# STM32_microcontroller_IOs.net
KiCad netlist of a schematic drawn in Altium Designer
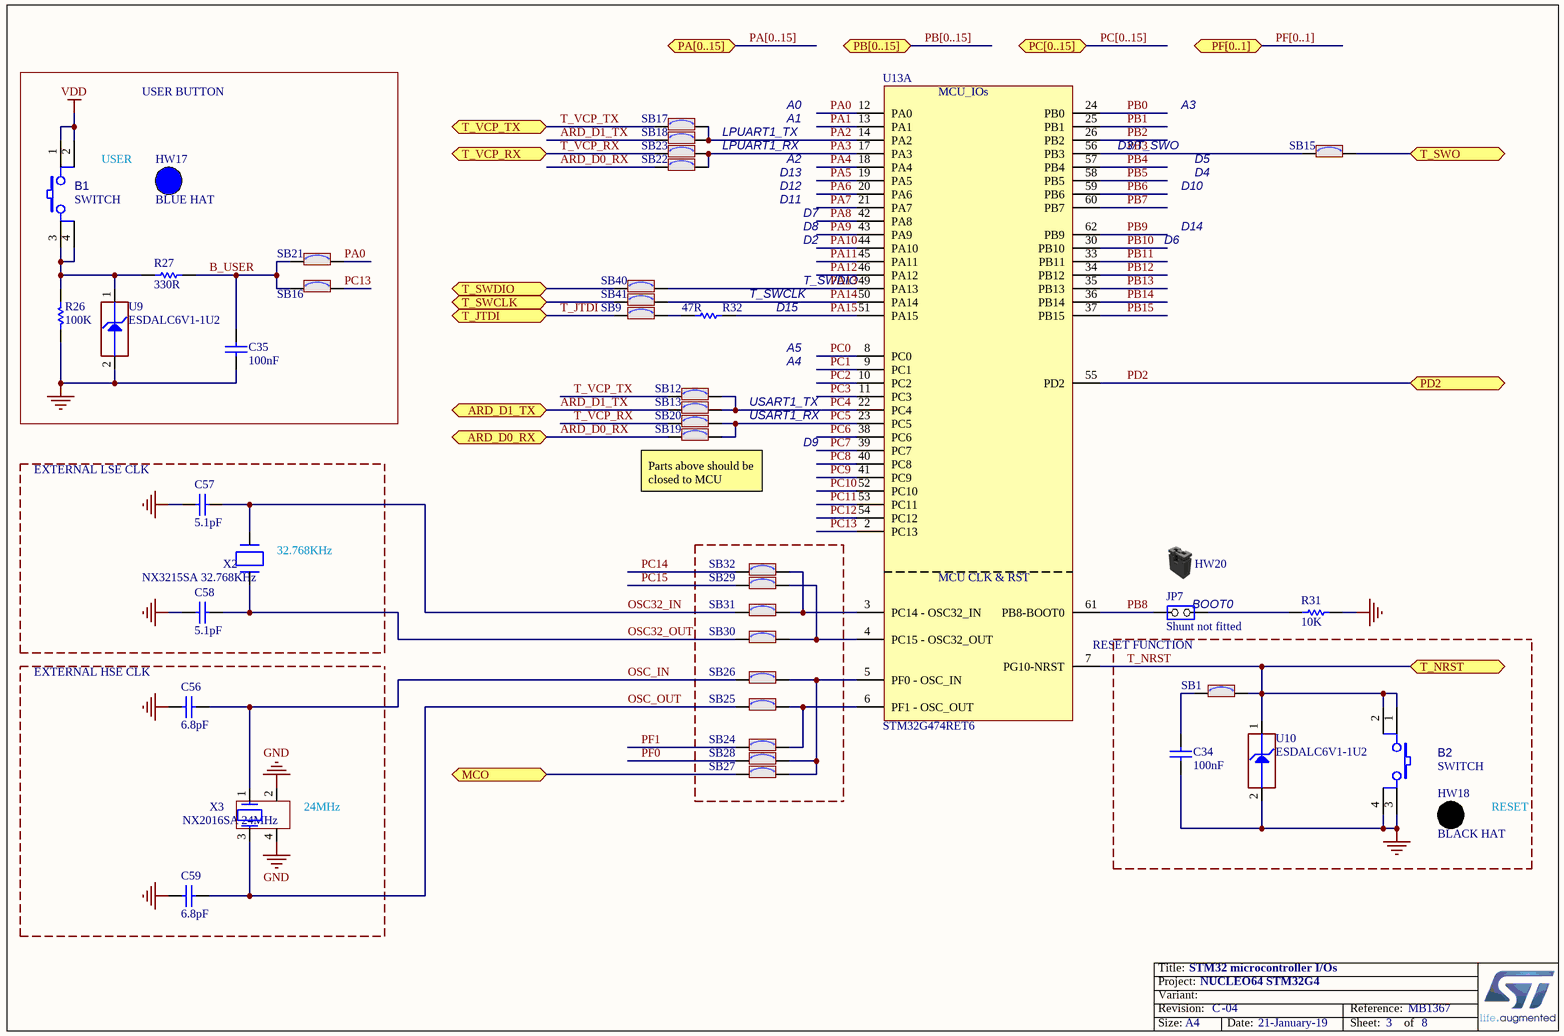
[diagram p0: STM32_microcontroller_IOs.SchDoc]

(export (version "E")
  (design (tool "Eeschema 10.0.6"))
  (components
    (comp (ref "B1")
      (value "SWITCH")
      (footprint "SWI_WEALTHMETAL_TD-0341_4P_BLUE")
      (description "Non-Open Push-Button 0.1A 24V")
      (fields
        (field (name "INTERNAL_PART_NUMBER") "MCD-00002")
        (field (name "MANUFACTURER_PART_NUMBER") "TD-0341")
        (field (name "PROVIDED_BY") "SUBCO")
      )
      (libsource (lib "MCD_PARTS_database") (part "SW-PUSH-CMS"))
    )
    (comp (ref "B2")
      (value "SWITCH")
      (footprint "SWI_WEALTHMETAL_TD-0341_4P_BLACK")
      (description "Non-Open Push-Button 0.1A 24V BLACK")
      (fields
        (field (name "INTERNAL_PART_NUMBER") "MCD-00001")
        (field (name "MANUFACTURER_PART_NUMBER") "TD-0341")
        (field (name "PROVIDED_BY") "SUBCO")
      )
      (libsource (lib "MCD_PARTS_database") (part "SW-PUSH-CMS"))
    )
    (comp (ref "C34")
      (value "100nF")
      (footprint "C0402")
      (description "Capacitor, MLCC, 100nF, 16V, X7R, 10%, 0402, T=0,5mm")
      (fields
        (field (name "INTERNAL_PART_NUMBER") "MCD-00102")
        (field (name "MANUFACTURER_PART_NUMBER") "CC0402KRX7R7BB104")
        (field (name "PROVIDED_BY") "Subcon")
      )
      (libsource (lib "MCD_PARTS_database") (part "Capacitor"))
    )
    (comp (ref "C35")
      (value "100nF")
      (footprint "C0402")
      (description "Capacitor, MLCC, 100nF, 16V, X7R, 10%, 0402, T=0,5mm")
      (fields
        (field (name "INTERNAL_PART_NUMBER") "MCD-00102")
        (field (name "MANUFACTURER_PART_NUMBER") "CC0402KRX7R7BB104")
        (field (name "PROVIDED_BY") "Subcon")
      )
      (libsource (lib "MCD_PARTS_database") (part "Capacitor"))
    )
    (comp (ref "C56")
      (value "6.8pF")
      (footprint "C0402")
      (description "Capacitor, MLCC, 6.8pF, 50V, NPO, +-0.25pF, 0402, T=0.5mm")
      (fields
        (field (name "INTERNAL_PART_NUMBER") "MCD-00674")
        (field (name "MANUFACTURER_PART_NUMBER") "CC0402CRNPO9BN6R8")
        (field (name "PROVIDED_BY") "SUBCO")
      )
      (libsource (lib "MCD_PARTS_database") (part "Capacitor"))
    )
    (comp (ref "C57")
      (value "5.1pF")
      (footprint "C0402")
      (description "Capacitor, MLCC, 5.1pF, 50V, NPO, +-0.25pF, 0402, T=0.5mm")
      (fields
        (field (name "INTERNAL_PART_NUMBER") "MCD-00003")
        (field (name "MANUFACTURER_PART_NUMBER") "CC0402CRNPO9BN5R1")
        (field (name "PROVIDED_BY") "SUBCO")
      )
      (libsource (lib "MCD_PARTS_database") (part "Capacitor"))
    )
    (comp (ref "C58")
      (value "5.1pF")
      (footprint "C0402")
      (description "Capacitor, MLCC, 5.1pF, 50V, NPO, +-0.25pF, 0402, T=0.5mm")
      (fields
        (field (name "INTERNAL_PART_NUMBER") "MCD-00003")
        (field (name "MANUFACTURER_PART_NUMBER") "CC0402CRNPO9BN5R1")
        (field (name "PROVIDED_BY") "SUBCO")
      )
      (libsource (lib "MCD_PARTS_database") (part "Capacitor"))
    )
    (comp (ref "C59")
      (value "6.8pF")
      (footprint "C0402")
      (description "Capacitor, MLCC, 6.8pF, 50V, NPO, +-0.25pF, 0402, T=0.5mm")
      (fields
        (field (name "INTERNAL_PART_NUMBER") "MCD-00674")
        (field (name "MANUFACTURER_PART_NUMBER") "CC0402CRNPO9BN6R8")
        (field (name "PROVIDED_BY") "SUBCO")
      )
      (libsource (lib "MCD_PARTS_database") (part "Capacitor"))
    )
    (comp (ref "HW17")
      (value "BLUE HAT")
      (description "Blue Hat for switch TD0341X-G01-BLU")
      (fields
        (field (name "INTERNAL_PART_NUMBER") "MCD-00634")
        (field (name "MANUFACTURER_PART_NUMBER") "988.16.09.3.00002_SH-517")
        (field (name "PROVIDED_BY") "SUBCO")
      )
      (libsource (lib "MCD_PARTS_database") (part "BUTTON_HAT_BLUE"))
    )
    (comp (ref "HW18")
      (value "BLACK HAT")
      (description "Black Hat for switch TD0341X-G01-BLA")
      (fields
        (field (name "INTERNAL_PART_NUMBER") "MCD-00635")
        (field (name "MANUFACTURER_PART_NUMBER") "988.16.09.3.00003_SH-517")
        (field (name "PROVIDED_BY") "SUBCO")
      )
      (libsource (lib "MCD_PARTS_database") (part "BUTTON_HAT_BLACK"))
    )
    (comp (ref "HW20")
      (value "~")
      (description "SHUNT 2.54mm BLACK")
      (fields
        (field (name "INTERNAL_PART_NUMBER") "MCD-00043")
        (field (name "MANUFACTURER_PART_NUMBER") "SNT-100-BK-G")
        (field (name "PROVIDED_BY") "Subcon")
      )
      (libsource (lib "MCD_PARTS_database") (part "Shunt Black 2.54mm"))
    )
    (comp (ref "JP7")
      (value "Shunt not fitted")
      (footprint "CON_SAMTEC_TSW-102-07-G-S")
      (description "Header, 2x1, 2,54mm, VR, TH, Height 5.84mm/2.54mm")
      (fields
        (field (name "INTERNAL_PART_NUMBER") "MCD-00045")
        (field (name "MANUFACTURER_PART_NUMBER") "TSW-102-07-x-S")
        (field (name "PROVIDED_BY") "Subcon")
      )
      (libsource (lib "MCD_PARTS_database") (part "Jumper_Header 2x1"))
    )
    (comp (ref "R26")
      (value "100K")
      (footprint "R0603")
      (description "Resistor,100K,0603,1%,1/10W")
      (fields
        (field (name "INTERNAL_PART_NUMBER") "MCD-00223")
        (field (name "MANUFACTURER_PART_NUMBER") "RC0603FR-07100KL")
        (field (name "PROVIDED_BY") "Subcon")
      )
      (libsource (lib "MCD_PARTS_database") (part "Resistor"))
    )
    (comp (ref "R27")
      (value "330R")
      (footprint "R0603")
      (description "Resistor,330R,0603,1%,1/10W")
      (fields
        (field (name "INTERNAL_PART_NUMBER") "MCD-00197")
        (field (name "MANUFACTURER_PART_NUMBER") "RC0603FR-07330RL")
        (field (name "PROVIDED_BY") "Subcon")
      )
      (libsource (lib "MCD_PARTS_database") (part "Resistor"))
    )
    (comp (ref "R31")
      (value "10K")
      (footprint "R0603")
      (description "Resistor,10K,0603,1%,1/10W")
      (fields
        (field (name "INTERNAL_PART_NUMBER") "MCD-00220")
        (field (name "MANUFACTURER_PART_NUMBER") "RC0603FR-0710KL")
        (field (name "PROVIDED_BY") "Subcon")
      )
      (libsource (lib "MCD_PARTS_database") (part "Resistor"))
    )
    (comp (ref "R32")
      (value "47R")
      (footprint "R0402")
      (description "Resistor,47R,0402,1%,1/16W")
      (fields
        (field (name "INTERNAL_PART_NUMBER") "MCD-00481")
        (field (name "MANUFACTURER_PART_NUMBER") "RC0402FR-0747RL")
        (field (name "PROVIDED_BY") "SUBCO")
      )
      (libsource (lib "MCD_PARTS_database") (part "Resistor"))
    )
    (comp (ref "SB1")
      (value "~")
      (footprint "SOLDER-BRIDGE_R0603-0R")
      (description "Solder Bridge ON")
      (fields
        (field (name "INTERNAL_PART_NUMBER") "MCD-00071")
        (field (name "MANUFACTURER_PART_NUMBER") "RC0603JR-070RL")
        (field (name "PROVIDED_BY") "SUBCO")
      )
      (libsource (lib "MCD_PARTS_database") (part "SB_ON"))
    )
    (comp (ref "SB9")
      (value "~")
      (footprint "SOLDER-BRIDGE_R0603-0R")
      (description "Solder Bridge ON")
      (fields
        (field (name "INTERNAL_PART_NUMBER") "MCD-00071")
        (field (name "MANUFACTURER_PART_NUMBER") "RC0603JR-070RL")
        (field (name "PROVIDED_BY") "SUBCO")
      )
      (libsource (lib "MCD_PARTS_database") (part "SB_ON"))
    )
    (comp (ref "SB12")
      (value "~")
      (footprint "SOLDER-BRIDGE_R0603-0R")
      (description "Solder Bridge ON")
      (fields
        (field (name "INTERNAL_PART_NUMBER") "MCD-00071")
        (field (name "MANUFACTURER_PART_NUMBER") "RC0603JR-070RL")
        (field (name "PROVIDED_BY") "SUBCO")
      )
      (libsource (lib "MCD_PARTS_database") (part "SB_ON"))
    )
    (comp (ref "SB13")
      (value "~")
      (footprint "SOLDER-BRIDGE_R0603-0R")
      (description "Solder Bridge ON")
      (fields
        (field (name "INTERNAL_PART_NUMBER") "MCD-00071")
        (field (name "MANUFACTURER_PART_NUMBER") "RC0603JR-070RL")
        (field (name "PROVIDED_BY") "SUBCO")
      )
      (libsource (lib "") (part "SB_ON_1"))
    )
    (comp (ref "SB15")
      (value "~")
      (footprint "SOLDER-BRIDGE_R0603-0R")
      (description "Solder Bridge ON")
      (fields
        (field (name "INTERNAL_PART_NUMBER") "MCD-00071")
        (field (name "MANUFACTURER_PART_NUMBER") "RC0603JR-070RL")
        (field (name "PROVIDED_BY") "SUBCO")
      )
      (libsource (lib "MCD_PARTS_database") (part "SB_ON"))
    )
    (comp (ref "SB16")
      (value "~")
      (footprint "SOLDER-BRIDGE_R0603-0R")
      (description "Solder Bridge ON")
      (fields
        (field (name "INTERNAL_PART_NUMBER") "MCD-00071")
        (field (name "MANUFACTURER_PART_NUMBER") "RC0603JR-070RL")
        (field (name "PROVIDED_BY") "SUBCO")
      )
      (libsource (lib "MCD_PARTS_database") (part "SB_ON"))
    )
    (comp (ref "SB17")
      (value "~")
      (footprint "SOLDER-BRIDGE_R0603-0R")
      (description "Solder Bridge ON")
      (fields
        (field (name "INTERNAL_PART_NUMBER") "MCD-00071")
        (field (name "MANUFACTURER_PART_NUMBER") "RC0603JR-070RL")
        (field (name "PROVIDED_BY") "SUBCO")
      )
      (libsource (lib "MCD_PARTS_database") (part "SB_ON"))
    )
    (comp (ref "SB18")
      (value "~")
      (footprint "SOLDER-BRIDGE_R0603-0R")
      (description "Solder Bridge ON")
      (fields
        (field (name "INTERNAL_PART_NUMBER") "MCD-00071")
        (field (name "MANUFACTURER_PART_NUMBER") "RC0603JR-070RL")
        (field (name "PROVIDED_BY") "SUBCO")
      )
      (libsource (lib "") (part "SB_ON_1"))
    )
    (comp (ref "SB19")
      (value "~")
      (footprint "SOLDER-BRIDGE_R0603-0R")
      (description "Solder Bridge ON")
      (fields
        (field (name "INTERNAL_PART_NUMBER") "MCD-00071")
        (field (name "MANUFACTURER_PART_NUMBER") "RC0603JR-070RL")
        (field (name "PROVIDED_BY") "SUBCO")
      )
      (libsource (lib "") (part "SB_ON_1"))
    )
    (comp (ref "SB20")
      (value "~")
      (footprint "SOLDER-BRIDGE_R0603-0R")
      (description "Solder Bridge ON")
      (fields
        (field (name "INTERNAL_PART_NUMBER") "MCD-00071")
        (field (name "MANUFACTURER_PART_NUMBER") "RC0603JR-070RL")
        (field (name "PROVIDED_BY") "SUBCO")
      )
      (libsource (lib "MCD_PARTS_database") (part "SB_ON"))
    )
    (comp (ref "SB21")
      (value "~")
      (footprint "SOLDER-BRIDGE_R0603-0R")
      (description "Solder Bridge ON")
      (fields
        (field (name "INTERNAL_PART_NUMBER") "MCD-00071")
        (field (name "MANUFACTURER_PART_NUMBER") "RC0603JR-070RL")
        (field (name "PROVIDED_BY") "SUBCO")
      )
      (libsource (lib "MCD_PARTS_database") (part "SB_ON"))
    )
    (comp (ref "SB22")
      (value "~")
      (footprint "SOLDER-BRIDGE_R0603-0R")
      (description "Solder Bridge ON")
      (fields
        (field (name "INTERNAL_PART_NUMBER") "MCD-00071")
        (field (name "MANUFACTURER_PART_NUMBER") "RC0603JR-070RL")
        (field (name "PROVIDED_BY") "SUBCO")
      )
      (libsource (lib "") (part "SB_ON_1"))
    )
    (comp (ref "SB23")
      (value "~")
      (footprint "SOLDER-BRIDGE_R0603-0R")
      (description "Solder Bridge ON")
      (fields
        (field (name "INTERNAL_PART_NUMBER") "MCD-00071")
        (field (name "MANUFACTURER_PART_NUMBER") "RC0603JR-070RL")
        (field (name "PROVIDED_BY") "SUBCO")
      )
      (libsource (lib "MCD_PARTS_database") (part "SB_ON"))
    )
    (comp (ref "SB24")
      (value "~")
      (footprint "SOLDER-BRIDGE_R0603-0R")
      (description "Solder Bridge ON")
      (fields
        (field (name "INTERNAL_PART_NUMBER") "MCD-00071")
        (field (name "MANUFACTURER_PART_NUMBER") "RC0603JR-070RL")
        (field (name "PROVIDED_BY") "SUBCO")
      )
      (libsource (lib "MCD_PARTS_database") (part "SB_ON"))
    )
    (comp (ref "SB25")
      (value "~")
      (footprint "SOLDER-BRIDGE_R0603-0R")
      (description "Solder Bridge ON")
      (fields
        (field (name "INTERNAL_PART_NUMBER") "MCD-00071")
        (field (name "MANUFACTURER_PART_NUMBER") "RC0603JR-070RL")
        (field (name "PROVIDED_BY") "SUBCO")
      )
      (libsource (lib "MCD_PARTS_database") (part "SB_ON"))
    )
    (comp (ref "SB26")
      (value "~")
      (footprint "SOLDER-BRIDGE_R0603-0R")
      (description "Solder Bridge ON")
      (fields
        (field (name "INTERNAL_PART_NUMBER") "MCD-00071")
        (field (name "MANUFACTURER_PART_NUMBER") "RC0603JR-070RL")
        (field (name "PROVIDED_BY") "SUBCO")
      )
      (libsource (lib "MCD_PARTS_database") (part "SB_ON"))
    )
    (comp (ref "SB27")
      (value "~")
      (footprint "SOLDER-BRIDGE_R0603-0R")
      (description "Solder Bridge ON")
      (fields
        (field (name "INTERNAL_PART_NUMBER") "MCD-00071")
        (field (name "MANUFACTURER_PART_NUMBER") "RC0603JR-070RL")
        (field (name "PROVIDED_BY") "SUBCO")
      )
      (libsource (lib "MCD_PARTS_database") (part "SB_ON"))
    )
    (comp (ref "SB28")
      (value "~")
      (footprint "SOLDER-BRIDGE_R0603-0R")
      (description "Solder Bridge ON")
      (fields
        (field (name "INTERNAL_PART_NUMBER") "MCD-00071")
        (field (name "MANUFACTURER_PART_NUMBER") "RC0603JR-070RL")
        (field (name "PROVIDED_BY") "SUBCO")
      )
      (libsource (lib "MCD_PARTS_database") (part "SB_ON"))
    )
    (comp (ref "SB29")
      (value "~")
      (footprint "SOLDER-BRIDGE_R0603-0R")
      (description "Solder Bridge ON")
      (fields
        (field (name "INTERNAL_PART_NUMBER") "MCD-00071")
        (field (name "MANUFACTURER_PART_NUMBER") "RC0603JR-070RL")
        (field (name "PROVIDED_BY") "SUBCO")
      )
      (libsource (lib "MCD_PARTS_database") (part "SB_ON"))
    )
    (comp (ref "SB30")
      (value "~")
      (footprint "SOLDER-BRIDGE_R0603-0R")
      (description "Solder Bridge ON")
      (fields
        (field (name "INTERNAL_PART_NUMBER") "MCD-00071")
        (field (name "MANUFACTURER_PART_NUMBER") "RC0603JR-070RL")
        (field (name "PROVIDED_BY") "SUBCO")
      )
      (libsource (lib "MCD_PARTS_database") (part "SB_ON"))
    )
    (comp (ref "SB31")
      (value "~")
      (footprint "SOLDER-BRIDGE_R0603-0R")
      (description "Solder Bridge ON")
      (fields
        (field (name "INTERNAL_PART_NUMBER") "MCD-00071")
        (field (name "MANUFACTURER_PART_NUMBER") "RC0603JR-070RL")
        (field (name "PROVIDED_BY") "SUBCO")
      )
      (libsource (lib "MCD_PARTS_database") (part "SB_ON"))
    )
    (comp (ref "SB32")
      (value "~")
      (footprint "SOLDER-BRIDGE_R0603-0R")
      (description "Solder Bridge ON")
      (fields
        (field (name "INTERNAL_PART_NUMBER") "MCD-00071")
        (field (name "MANUFACTURER_PART_NUMBER") "RC0603JR-070RL")
        (field (name "PROVIDED_BY") "SUBCO")
      )
      (libsource (lib "MCD_PARTS_database") (part "SB_ON"))
    )
    (comp (ref "SB40")
      (value "~")
      (footprint "SOLDER-BRIDGE_R0603-0R")
      (description "Solder Bridge ON")
      (fields
        (field (name "INTERNAL_PART_NUMBER") "MCD-00071")
        (field (name "MANUFACTURER_PART_NUMBER") "RC0603JR-070RL")
        (field (name "PROVIDED_BY") "SUBCO")
      )
      (libsource (lib "MCD_PARTS_database") (part "SB_ON"))
    )
    (comp (ref "SB41")
      (value "~")
      (footprint "SOLDER-BRIDGE_R0603-0R")
      (description "Solder Bridge ON")
      (fields
        (field (name "INTERNAL_PART_NUMBER") "MCD-00071")
        (field (name "MANUFACTURER_PART_NUMBER") "RC0603JR-070RL")
        (field (name "PROVIDED_BY") "SUBCO")
      )
      (libsource (lib "MCD_PARTS_database") (part "SB_ON"))
    )
    (comp (ref "U9")
      (value "ESDALC6V1-1U2")
      (footprint "ESD_ST0201")
      (description "ESD protection 6V1")
      (fields
        (field (name "INTERNAL_PART_NUMBER") "MCD-00170")
        (field (name "MANUFACTURER") "STMICROELECTRONICS")
        (field (name "PROVIDED_BY") "Subcon")
      )
      (libsource (lib "MCD_PARTS_database") (part "ESD-TRANSIL"))
    )
    (comp (ref "U10")
      (value "ESDALC6V1-1U2")
      (footprint "ESD_ST0201")
      (description "ESD protection 6V1")
      (fields
        (field (name "INTERNAL_PART_NUMBER") "MCD-00170")
        (field (name "MANUFACTURER") "STMICROELECTRONICS")
        (field (name "PROVIDED_BY") "Subcon")
      )
      (libsource (lib "MCD_PARTS_database") (part "ESD-TRANSIL"))
    )
    (comp (ref "U13")
      (value "STM32G474RET6")
      (footprint "ICC_LQFP64_10X10_P050_SOCKET_YAMAICHI_IC149-064-069-B5_NM")
      (description "STM32G474, LQFP64 package,  3D IC footprint with 2D socket footprint.")
      (fields
        (field (name "INTERNAL_PART_NUMBER") "MCD-01243")
        (field (name "MANUFACTURER") "STMICROELECTRONICS")
        (field (name "PROVIDED_BY") "SUBCO with ST control")
      )
      (libsource (lib "MCD_PARTS_database") (part "STM32G4xx_LQFP64"))
    )
    (comp (ref "X2")
      (value "NX3215SA 32.768KHz")
      (footprint "CRY_NX3215SA_2P")
      (description "Crystal 32.768kHz, 6pF, +-20ppm, 50Kohms max, SMD")
      (fields
        (field (name "INTERNAL_PART_NUMBER") "MCD-00091")
        (field (name "MANUFACTURER_PART_NUMBER") "NX3215SA 32.768KHz EXS00A-MU00525")
        (field (name "PROVIDED_BY") "SUBCO")
      )
      (libsource (lib "MCD_PARTS_database") (part "XTAL_2_PINS"))
    )
    (comp (ref "X3")
      (value "NX2016SA 24MHz")
      (footprint "CRY_NX2016SA_4P")
      (description "Crystal 24MHz, 6pF, +-20ppm, 80ohms max, SMD")
      (fields
        (field (name "INTERNAL_PART_NUMBER") "MCD-01036")
        (field (name "MANUFACTURER_PART_NUMBER") "NX2016SA 24MHz EXS00A-CS10820")
        (field (name "PROVIDED_BY") "SUBCO")
      )
      (libsource (lib "MCD_PARTS_database") (part "XTAL_4_PINS"))
    )
  )
  (nets
    (net (code "1") (name "/ARD_D0_RX") (class "Default")
      (node (ref "SB19") (pin "2") (pinfunction "2_2") (pintype "passive"))
      (node (ref "SB22") (pin "2") (pinfunction "2_2") (pintype "passive"))
    )
    (net (code "2") (name "/ARD_D1_TX") (class "Default")
      (node (ref "SB13") (pin "2") (pinfunction "2_2") (pintype "passive"))
      (node (ref "SB18") (pin "2") (pinfunction "2_2") (pintype "passive"))
    )
    (net (code "3") (name "/B_USER") (class "Default")
      (node (ref "C35") (pin "2") (pinfunction "2_2") (pintype "passive"))
      (node (ref "R27") (pin "2") (pinfunction "2_2") (pintype "passive"))
      (node (ref "SB16") (pin "1") (pinfunction "1_1") (pintype "passive"))
      (node (ref "SB21") (pin "1") (pinfunction "1_1") (pintype "passive"))
    )
    (net (code "4") (name "/MCO") (class "Default")
      (node (ref "SB27") (pin "1") (pinfunction "1_1") (pintype "passive"))
    )
    (net (code "5") (name "/OSC32_IN") (class "Default")
      (node (ref "C57") (pin "1") (pinfunction "1_1") (pintype "passive"))
      (node (ref "SB31") (pin "1") (pinfunction "1_1") (pintype "passive"))
      (node (ref "X2") (pin "2") (pinfunction "X2_2") (pintype "passive"))
    )
    (net (code "6") (name "/OSC32_OUT") (class "Default")
      (node (ref "C58") (pin "1") (pinfunction "1_1") (pintype "passive"))
      (node (ref "SB30") (pin "1") (pinfunction "1_1") (pintype "passive"))
      (node (ref "X2") (pin "1") (pinfunction "X1_1") (pintype "passive"))
    )
    (net (code "7") (name "/OSC_IN") (class "Default")
      (node (ref "C56") (pin "2") (pinfunction "2_2") (pintype "passive"))
      (node (ref "SB26") (pin "1") (pinfunction "1_1") (pintype "passive"))
      (node (ref "X3") (pin "1") (pinfunction "1_1") (pintype "passive"))
    )
    (net (code "8") (name "/OSC_OUT") (class "Default")
      (node (ref "C59") (pin "2") (pinfunction "2_2") (pintype "passive"))
      (node (ref "SB25") (pin "1") (pinfunction "1_1") (pintype "passive"))
      (node (ref "X3") (pin "3") (pinfunction "3_3") (pintype "passive"))
    )
    (net (code "9") (name "/PA0") (class "Default")
      (node (ref "SB21") (pin "2") (pinfunction "2_2") (pintype "passive"))
      (node (ref "U13") (pin "12") (pinfunction "PA0_12") (pintype "passive"))
    )
    (net (code "10") (name "/PA1") (class "Default")
      (node (ref "U13") (pin "13") (pinfunction "PA1_13") (pintype "passive"))
    )
    (net (code "11") (name "/PA2") (class "Default")
      (node (ref "SB17") (pin "2") (pinfunction "2_2") (pintype "passive"))
      (node (ref "SB18") (pin "1") (pinfunction "1_1") (pintype "passive"))
      (node (ref "U13") (pin "14") (pinfunction "PA2_14") (pintype "passive"))
    )
    (net (code "12") (name "/PA3") (class "Default")
      (node (ref "SB22") (pin "1") (pinfunction "1_1") (pintype "passive"))
      (node (ref "SB23") (pin "2") (pinfunction "2_2") (pintype "passive"))
      (node (ref "U13") (pin "17") (pinfunction "PA3_17") (pintype "passive"))
    )
    (net (code "13") (name "/PA4") (class "Default")
      (node (ref "U13") (pin "18") (pinfunction "PA4_18") (pintype "passive"))
    )
    (net (code "14") (name "/PA5") (class "Default")
      (node (ref "U13") (pin "19") (pinfunction "PA5_19") (pintype "passive"))
    )
    (net (code "15") (name "/PA6") (class "Default")
      (node (ref "U13") (pin "20") (pinfunction "PA6_20") (pintype "passive"))
    )
    (net (code "16") (name "/PA7") (class "Default")
      (node (ref "U13") (pin "21") (pinfunction "PA7_21") (pintype "passive"))
    )
    (net (code "17") (name "/PA8") (class "Default")
      (node (ref "U13") (pin "42") (pinfunction "PA8_42") (pintype "passive"))
    )
    (net (code "18") (name "/PA9") (class "Default")
      (node (ref "U13") (pin "43") (pinfunction "PA9_43") (pintype "passive"))
    )
    (net (code "19") (name "/PA10") (class "Default")
      (node (ref "U13") (pin "44") (pinfunction "PA10_44") (pintype "passive"))
    )
    (net (code "20") (name "/PA11") (class "Default")
      (node (ref "U13") (pin "45") (pinfunction "PA11_45") (pintype "passive"))
    )
    (net (code "21") (name "/PA12") (class "Default")
      (node (ref "U13") (pin "46") (pinfunction "PA12_46") (pintype "passive"))
    )
    (net (code "22") (name "/PA13") (class "Default")
      (node (ref "SB40") (pin "2") (pinfunction "2_2") (pintype "passive"))
      (node (ref "U13") (pin "49") (pinfunction "PA13_49") (pintype "passive"))
    )
    (net (code "23") (name "/PA14") (class "Default")
      (node (ref "SB41") (pin "2") (pinfunction "2_2") (pintype "passive"))
      (node (ref "U13") (pin "50") (pinfunction "PA14_50") (pintype "passive"))
    )
    (net (code "24") (name "/PA15") (class "Default")
      (node (ref "R32") (pin "2") (pinfunction "2_2") (pintype "passive"))
      (node (ref "U13") (pin "51") (pinfunction "PA15_51") (pintype "passive"))
    )
    (net (code "26") (name "/PB0") (class "Default")
      (node (ref "U13") (pin "24") (pinfunction "PB0_24") (pintype "passive"))
    )
    (net (code "27") (name "/PB1") (class "Default")
      (node (ref "U13") (pin "25") (pinfunction "PB1_25") (pintype "passive"))
    )
    (net (code "28") (name "/PB2") (class "Default")
      (node (ref "U13") (pin "26") (pinfunction "PB2_26") (pintype "passive"))
    )
    (net (code "29") (name "/PB3") (class "Default")
      (node (ref "SB15") (pin "1") (pinfunction "1_1") (pintype "passive"))
      (node (ref "U13") (pin "56") (pinfunction "PB3_56") (pintype "passive"))
    )
    (net (code "30") (name "/PB4") (class "Default")
      (node (ref "U13") (pin "57") (pinfunction "PB4_57") (pintype "passive"))
    )
    (net (code "31") (name "/PB5") (class "Default")
      (node (ref "U13") (pin "58") (pinfunction "PB5_58") (pintype "passive"))
    )
    (net (code "32") (name "/PB6") (class "Default")
      (node (ref "U13") (pin "59") (pinfunction "PB6_59") (pintype "passive"))
    )
    (net (code "33") (name "/PB7") (class "Default")
      (node (ref "U13") (pin "60") (pinfunction "PB7_60") (pintype "passive"))
    )
    (net (code "34") (name "/PB8") (class "Default")
      (node (ref "JP7") (pin "1") (pinfunction "COMMON_1") (pintype "passive"))
      (node (ref "U13") (pin "61") (pinfunction "PB8-BOOT0_61") (pintype "passive"))
    )
    (net (code "35") (name "/PB9") (class "Default")
      (node (ref "U13") (pin "62") (pinfunction "PB9_62") (pintype "passive"))
    )
    (net (code "36") (name "/PB10") (class "Default")
      (node (ref "U13") (pin "30") (pinfunction "PB10_30") (pintype "passive"))
    )
    (net (code "37") (name "/PB11") (class "Default")
      (node (ref "U13") (pin "33") (pinfunction "PB11_33") (pintype "passive"))
    )
    (net (code "38") (name "/PB12") (class "Default")
      (node (ref "U13") (pin "34") (pinfunction "PB12_34") (pintype "passive"))
    )
    (net (code "39") (name "/PB13") (class "Default")
      (node (ref "U13") (pin "35") (pinfunction "PB13_35") (pintype "passive"))
    )
    (net (code "40") (name "/PB14") (class "Default")
      (node (ref "U13") (pin "36") (pinfunction "PB14_36") (pintype "passive"))
    )
    (net (code "41") (name "/PB15") (class "Default")
      (node (ref "U13") (pin "37") (pinfunction "PB15_37") (pintype "passive"))
    )
    (net (code "43") (name "/PC0") (class "Default")
      (node (ref "U13") (pin "8") (pinfunction "PC0_8") (pintype "passive"))
    )
    (net (code "44") (name "/PC1") (class "Default")
      (node (ref "U13") (pin "9") (pinfunction "PC1_9") (pintype "passive"))
    )
    (net (code "45") (name "/PC2") (class "Default")
      (node (ref "U13") (pin "10") (pinfunction "PC2_10") (pintype "passive"))
    )
    (net (code "46") (name "/PC3") (class "Default")
      (node (ref "U13") (pin "11") (pinfunction "PC3_11") (pintype "passive"))
    )
    (net (code "47") (name "/PC4") (class "Default")
      (node (ref "SB12") (pin "2") (pinfunction "2_2") (pintype "passive"))
      (node (ref "SB13") (pin "1") (pinfunction "1_1") (pintype "passive"))
      (node (ref "U13") (pin "22") (pinfunction "PC4_22") (pintype "passive"))
    )
    (net (code "48") (name "/PC5") (class "Default")
      (node (ref "SB19") (pin "1") (pinfunction "1_1") (pintype "passive"))
      (node (ref "SB20") (pin "2") (pinfunction "2_2") (pintype "passive"))
      (node (ref "U13") (pin "23") (pinfunction "PC5_23") (pintype "passive"))
    )
    (net (code "49") (name "/PC6") (class "Default")
      (node (ref "U13") (pin "38") (pinfunction "PC6_38") (pintype "passive"))
    )
    (net (code "50") (name "/PC7") (class "Default")
      (node (ref "U13") (pin "39") (pinfunction "PC7_39") (pintype "passive"))
    )
    (net (code "51") (name "/PC8") (class "Default")
      (node (ref "U13") (pin "40") (pinfunction "PC8_40") (pintype "passive"))
    )
    (net (code "52") (name "/PC9") (class "Default")
      (node (ref "U13") (pin "41") (pinfunction "PC9_41") (pintype "passive"))
    )
    (net (code "53") (name "/PC10") (class "Default")
      (node (ref "U13") (pin "52") (pinfunction "PC10_52") (pintype "passive"))
    )
    (net (code "54") (name "/PC11") (class "Default")
      (node (ref "U13") (pin "53") (pinfunction "PC11_53") (pintype "passive"))
    )
    (net (code "55") (name "/PC12") (class "Default")
      (node (ref "U13") (pin "54") (pinfunction "PC12_54") (pintype "passive"))
    )
    (net (code "56") (name "/PC13") (class "Default")
      (node (ref "SB16") (pin "2") (pinfunction "2_2") (pintype "passive"))
      (node (ref "U13") (pin "2") (pinfunction "PC13_2") (pintype "passive"))
    )
    (net (code "57") (name "/PC14") (class "Default")
      (node (ref "SB32") (pin "1") (pinfunction "1_1") (pintype "passive"))
    )
    (net (code "58") (name "/PC15") (class "Default")
      (node (ref "SB29") (pin "1") (pinfunction "1_1") (pintype "passive"))
    )
    (net (code "60") (name "/PD2") (class "Default")
      (node (ref "U13") (pin "55") (pinfunction "PD2_55") (pintype "passive"))
    )
    (net (code "61") (name "/PF0") (class "Default")
      (node (ref "SB28") (pin "1") (pinfunction "1_1") (pintype "passive"))
    )
    (net (code "62") (name "/PF1") (class "Default")
      (node (ref "SB24") (pin "1") (pinfunction "1_1") (pintype "passive"))
    )
    (net (code "64") (name "/T_JTDI") (class "Default")
      (node (ref "SB9") (pin "1") (pinfunction "1_1") (pintype "passive"))
    )
    (net (code "65") (name "/T_NRST") (class "Default")
      (node (ref "B2") (pin "1") (pinfunction "1_1") (pintype "passive"))
      (node (ref "B2") (pin "2") (pinfunction "2_2") (pintype "passive"))
      (node (ref "SB1") (pin "2") (pinfunction "2_2") (pintype "passive"))
      (node (ref "U10") (pin "1") (pinfunction "IO1_1") (pintype "passive"))
      (node (ref "U13") (pin "7") (pinfunction "PG10-NRST_7") (pintype "passive"))
    )
    (net (code "66") (name "/T_SWCLK") (class "Default")
      (node (ref "SB41") (pin "1") (pinfunction "1_1") (pintype "passive"))
    )
    (net (code "67") (name "/T_SWDIO") (class "Default")
      (node (ref "SB40") (pin "1") (pinfunction "1_1") (pintype "passive"))
    )
    (net (code "68") (name "/T_SWO") (class "Default")
      (node (ref "SB15") (pin "2") (pinfunction "2_2") (pintype "passive"))
    )
    (net (code "69") (name "/T_VCP_RX") (class "Default")
      (node (ref "SB20") (pin "1") (pinfunction "1_1") (pintype "passive"))
      (node (ref "SB23") (pin "1") (pinfunction "1_1") (pintype "passive"))
    )
    (net (code "70") (name "/T_VCP_TX") (class "Default")
      (node (ref "SB12") (pin "1") (pinfunction "1_1") (pintype "passive"))
      (node (ref "SB17") (pin "1") (pinfunction "1_1") (pintype "passive"))
    )
    (net (code "71") (name "GND") (class "Default")
      (node (ref "B2") (pin "3") (pinfunction "3_3") (pintype "passive"))
      (node (ref "B2") (pin "4") (pinfunction "4_4") (pintype "passive"))
      (node (ref "C34") (pin "1") (pinfunction "1_1") (pintype "passive"))
      (node (ref "C35") (pin "1") (pinfunction "1_1") (pintype "passive"))
      (node (ref "C56") (pin "1") (pinfunction "1_1") (pintype "passive"))
      (node (ref "C57") (pin "2") (pinfunction "2_2") (pintype "passive"))
      (node (ref "C58") (pin "2") (pinfunction "2_2") (pintype "passive"))
      (node (ref "C59") (pin "1") (pinfunction "1_1") (pintype "passive"))
      (node (ref "R26") (pin "1") (pinfunction "1_1") (pintype "passive"))
      (node (ref "R31") (pin "1") (pinfunction "1_1") (pintype "passive"))
      (node (ref "U10") (pin "2") (pinfunction "GND_2") (pintype "passive"))
      (node (ref "U9") (pin "2") (pinfunction "GND_2") (pintype "passive"))
      (node (ref "X3") (pin "2") (pinfunction "2_2") (pintype "passive"))
      (node (ref "X3") (pin "4") (pinfunction "4_4") (pintype "passive"))
    )
    (net (code "72") (name "Net-(C34-Pad2)") (class "Default")
      (node (ref "C34") (pin "2") (pinfunction "2_2") (pintype "passive"))
      (node (ref "SB1") (pin "1") (pinfunction "1_1") (pintype "passive"))
    )
    (net (code "73") (name "Net-(JP7-NO)") (class "Default")
      (node (ref "JP7") (pin "2") (pinfunction "NO_2") (pintype "passive"))
      (node (ref "R31") (pin "2") (pinfunction "2_2") (pintype "passive"))
    )
    (net (code "74") (name "Net-(R32-Pad1)") (class "Default")
      (node (ref "R32") (pin "1") (pinfunction "1_1") (pintype "passive"))
      (node (ref "SB9") (pin "2") (pinfunction "2_2") (pintype "passive"))
    )
    (net (code "75") (name "Net-(U9-IO1)") (class "Default")
      (node (ref "B1") (pin "3") (pinfunction "3_3") (pintype "passive"))
      (node (ref "B1") (pin "4") (pinfunction "4_4") (pintype "passive"))
      (node (ref "R26") (pin "2") (pinfunction "2_2") (pintype "passive"))
      (node (ref "R27") (pin "1") (pinfunction "1_1") (pintype "passive"))
      (node (ref "U9") (pin "1") (pinfunction "IO1_1") (pintype "passive"))
    )
    (net (code "76") (name "Net-(U13A-PC14_-_OSC32_IN)") (class "Default")
      (node (ref "SB31") (pin "2") (pinfunction "2_2") (pintype "passive"))
      (node (ref "SB32") (pin "2") (pinfunction "2_2") (pintype "passive"))
      (node (ref "U13") (pin "3") (pinfunction "PC14_-_OSC32_IN_3") (pintype "passive"))
    )
    (net (code "77") (name "Net-(U13A-PC15_-_OSC32_OUT)") (class "Default")
      (node (ref "SB29") (pin "2") (pinfunction "2_2") (pintype "passive"))
      (node (ref "SB30") (pin "2") (pinfunction "2_2") (pintype "passive"))
      (node (ref "U13") (pin "4") (pinfunction "PC15_-_OSC32_OUT_4") (pintype "passive"))
    )
    (net (code "78") (name "Net-(U13A-PF0_-_OSC_IN)") (class "Default")
      (node (ref "SB26") (pin "2") (pinfunction "2_2") (pintype "passive"))
      (node (ref "SB27") (pin "2") (pinfunction "2_2") (pintype "passive"))
      (node (ref "SB28") (pin "2") (pinfunction "2_2") (pintype "passive"))
      (node (ref "U13") (pin "5") (pinfunction "PF0_-_OSC_IN_5") (pintype "passive"))
    )
    (net (code "79") (name "Net-(U13A-PF1_-_OSC_OUT)") (class "Default")
      (node (ref "SB24") (pin "2") (pinfunction "2_2") (pintype "passive"))
      (node (ref "SB25") (pin "2") (pinfunction "2_2") (pintype "passive"))
      (node (ref "U13") (pin "6") (pinfunction "PF1_-_OSC_OUT_6") (pintype "passive"))
    )
    (net (code "80") (name "VDD") (class "Default")
      (node (ref "B1") (pin "1") (pinfunction "1_1") (pintype "passive"))
      (node (ref "B1") (pin "2") (pinfunction "2_2") (pintype "passive"))
    )
  )
)
